# blinky.net
KiCad netlist of a schematic drawn in EAGLE
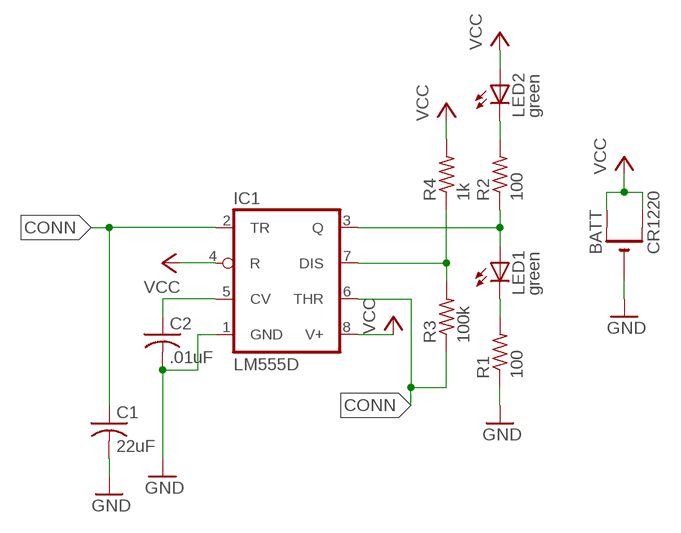
[diagram p0: schematic, sheet 1]

(export (version "E")
  (design (tool "Eeschema 10.0.6"))
  (components
    (comp (ref "BATT")
      (value "CR1220")
      (footprint "eagle-import:CR1220-SMD")
      (fields (field (name "MPN") "3080"))
      (libsource (lib "eagle-import") (part "CR1220SMT"))
    )
    (comp (ref "C1")
      (value "22uF")
      (footprint "eagle-import:C0805")
      (fields (field (name "MPN") "08056D226MAT2A"))
      (libsource (lib "eagle-import") (part "C-USC0805"))
    )
    (comp (ref "C2")
      (value ".01uF")
      (footprint "eagle-import:C0805")
      (fields (field (name "MPN") "GRM216R71H103KA01D"))
      (libsource (lib "eagle-import") (part "C-USC0805"))
    )
    (comp (ref "IC1")
      (value "LM555D")
      (footprint "eagle-import:SO08")
      (fields (field (name "MPN") "TLC555CD."))
      (libsource (lib "eagle-import") (part "555DLM"))
    )
    (comp (ref "LED1")
      (value "green")
      (footprint "eagle-import:CHIPLED_0805")
      (fields (field (name "MPN") "150080GS75000"))
      (libsource (lib "eagle-import") (part "LEDCHIPLED_0805"))
    )
    (comp (ref "LED2")
      (value "green")
      (footprint "eagle-import:CHIPLED_0805")
      (fields (field (name "MPN") "150080GS75000"))
      (libsource (lib "eagle-import") (part "LEDCHIPLED_0805"))
    )
    (comp (ref "R1")
      (value "100")
      (footprint "eagle-import:R0805")
      (fields (field (name "MPN") "CR0805-JW-101ELF"))
      (libsource (lib "eagle-import") (part "R-US_R0805"))
    )
    (comp (ref "R2")
      (value "100")
      (footprint "eagle-import:R0805")
      (fields (field (name "MPN") "CR0805-JW-101ELF"))
      (libsource (lib "eagle-import") (part "R-US_R0805"))
    )
    (comp (ref "R3")
      (value "100k")
      (footprint "eagle-import:R0805")
      (fields (field (name "MF") "FARNELL") (field (name "MPN") "MC 0.1W 0805 5% 100K"))
      (libsource (lib "eagle-import") (part "R-US_R0805"))
    )
    (comp (ref "R4")
      (value "1k")
      (footprint "eagle-import:R0805")
      (fields (field (name "MF") "VISHAY/DALE") (field (name "MPN") "CRCW08051K00FKTA"))
      (libsource (lib "eagle-import") (part "R-US_R0805"))
    )
  )
  (nets
    (net (code "1") (name "CONN") (class "Default")
      (node (ref "C1") (pin "1") (pinfunction "1_1") (pintype "passive"))
      (node (ref "IC1") (pin "2") (pinfunction "TR_2") (pintype "input"))
      (node (ref "IC1") (pin "6") (pinfunction "THR_6") (pintype "input"))
      (node (ref "R3") (pin "1") (pinfunction "1_1") (pintype "passive"))
    )
    (net (code "2") (name "GND") (class "Default")
      (node (ref "BATT") (pin "-") (pinfunction "-_-") (pintype "passive"))
      (node (ref "C1") (pin "2") (pinfunction "2_2") (pintype "passive"))
      (node (ref "C2") (pin "2") (pinfunction "2_2") (pintype "passive"))
      (node (ref "IC1") (pin "1") (pinfunction "GND_1") (pintype "power_in"))
      (node (ref "R1") (pin "1") (pinfunction "1_1") (pintype "passive"))
    )
    (net (code "3") (name "Net-(IC1-CV)") (class "Default")
      (node (ref "C2") (pin "1") (pinfunction "1_1") (pintype "passive"))
      (node (ref "IC1") (pin "5") (pinfunction "CV_5") (pintype "input"))
    )
    (net (code "4") (name "Net-(IC1-DIS)") (class "Default")
      (node (ref "IC1") (pin "7") (pinfunction "DIS_7") (pintype "input"))
      (node (ref "R3") (pin "2") (pinfunction "2_2") (pintype "passive"))
      (node (ref "R4") (pin "1") (pinfunction "1_1") (pintype "passive"))
    )
    (net (code "5") (name "Net-(IC1-Q)") (class "Default")
      (node (ref "IC1") (pin "3") (pinfunction "Q_3") (pintype "output"))
      (node (ref "LED1") (pin "A") (pinfunction "A_A") (pintype "passive"))
      (node (ref "R2") (pin "1") (pinfunction "1_1") (pintype "passive"))
    )
    (net (code "6") (name "Net-(LED1-PadC)") (class "Default")
      (node (ref "LED1") (pin "C") (pinfunction "C_C") (pintype "passive"))
      (node (ref "R1") (pin "2") (pinfunction "2_2") (pintype "passive"))
    )
    (net (code "7") (name "Net-(LED2-PadC)") (class "Default")
      (node (ref "LED2") (pin "C") (pinfunction "C_C") (pintype "passive"))
      (node (ref "R2") (pin "2") (pinfunction "2_2") (pintype "passive"))
    )
    (net (code "8") (name "VCC") (class "Default")
      (node (ref "BATT") (pin "+$1") (pinfunction "+_+$1") (pintype "passive"))
      (node (ref "BATT") (pin "+$2") (pinfunction "+1_+$2") (pintype "passive"))
      (node (ref "IC1") (pin "4") (pinfunction "R_4") (pintype "input"))
      (node (ref "IC1") (pin "8") (pinfunction "V+_8") (pintype "power_in"))
      (node (ref "LED2") (pin "A") (pinfunction "A_A") (pintype "passive"))
      (node (ref "R4") (pin "2") (pinfunction "2_2") (pintype "passive"))
    )
  )
)
